# arm_v4.net
KiCad netlist of a schematic drawn in Altium Designer
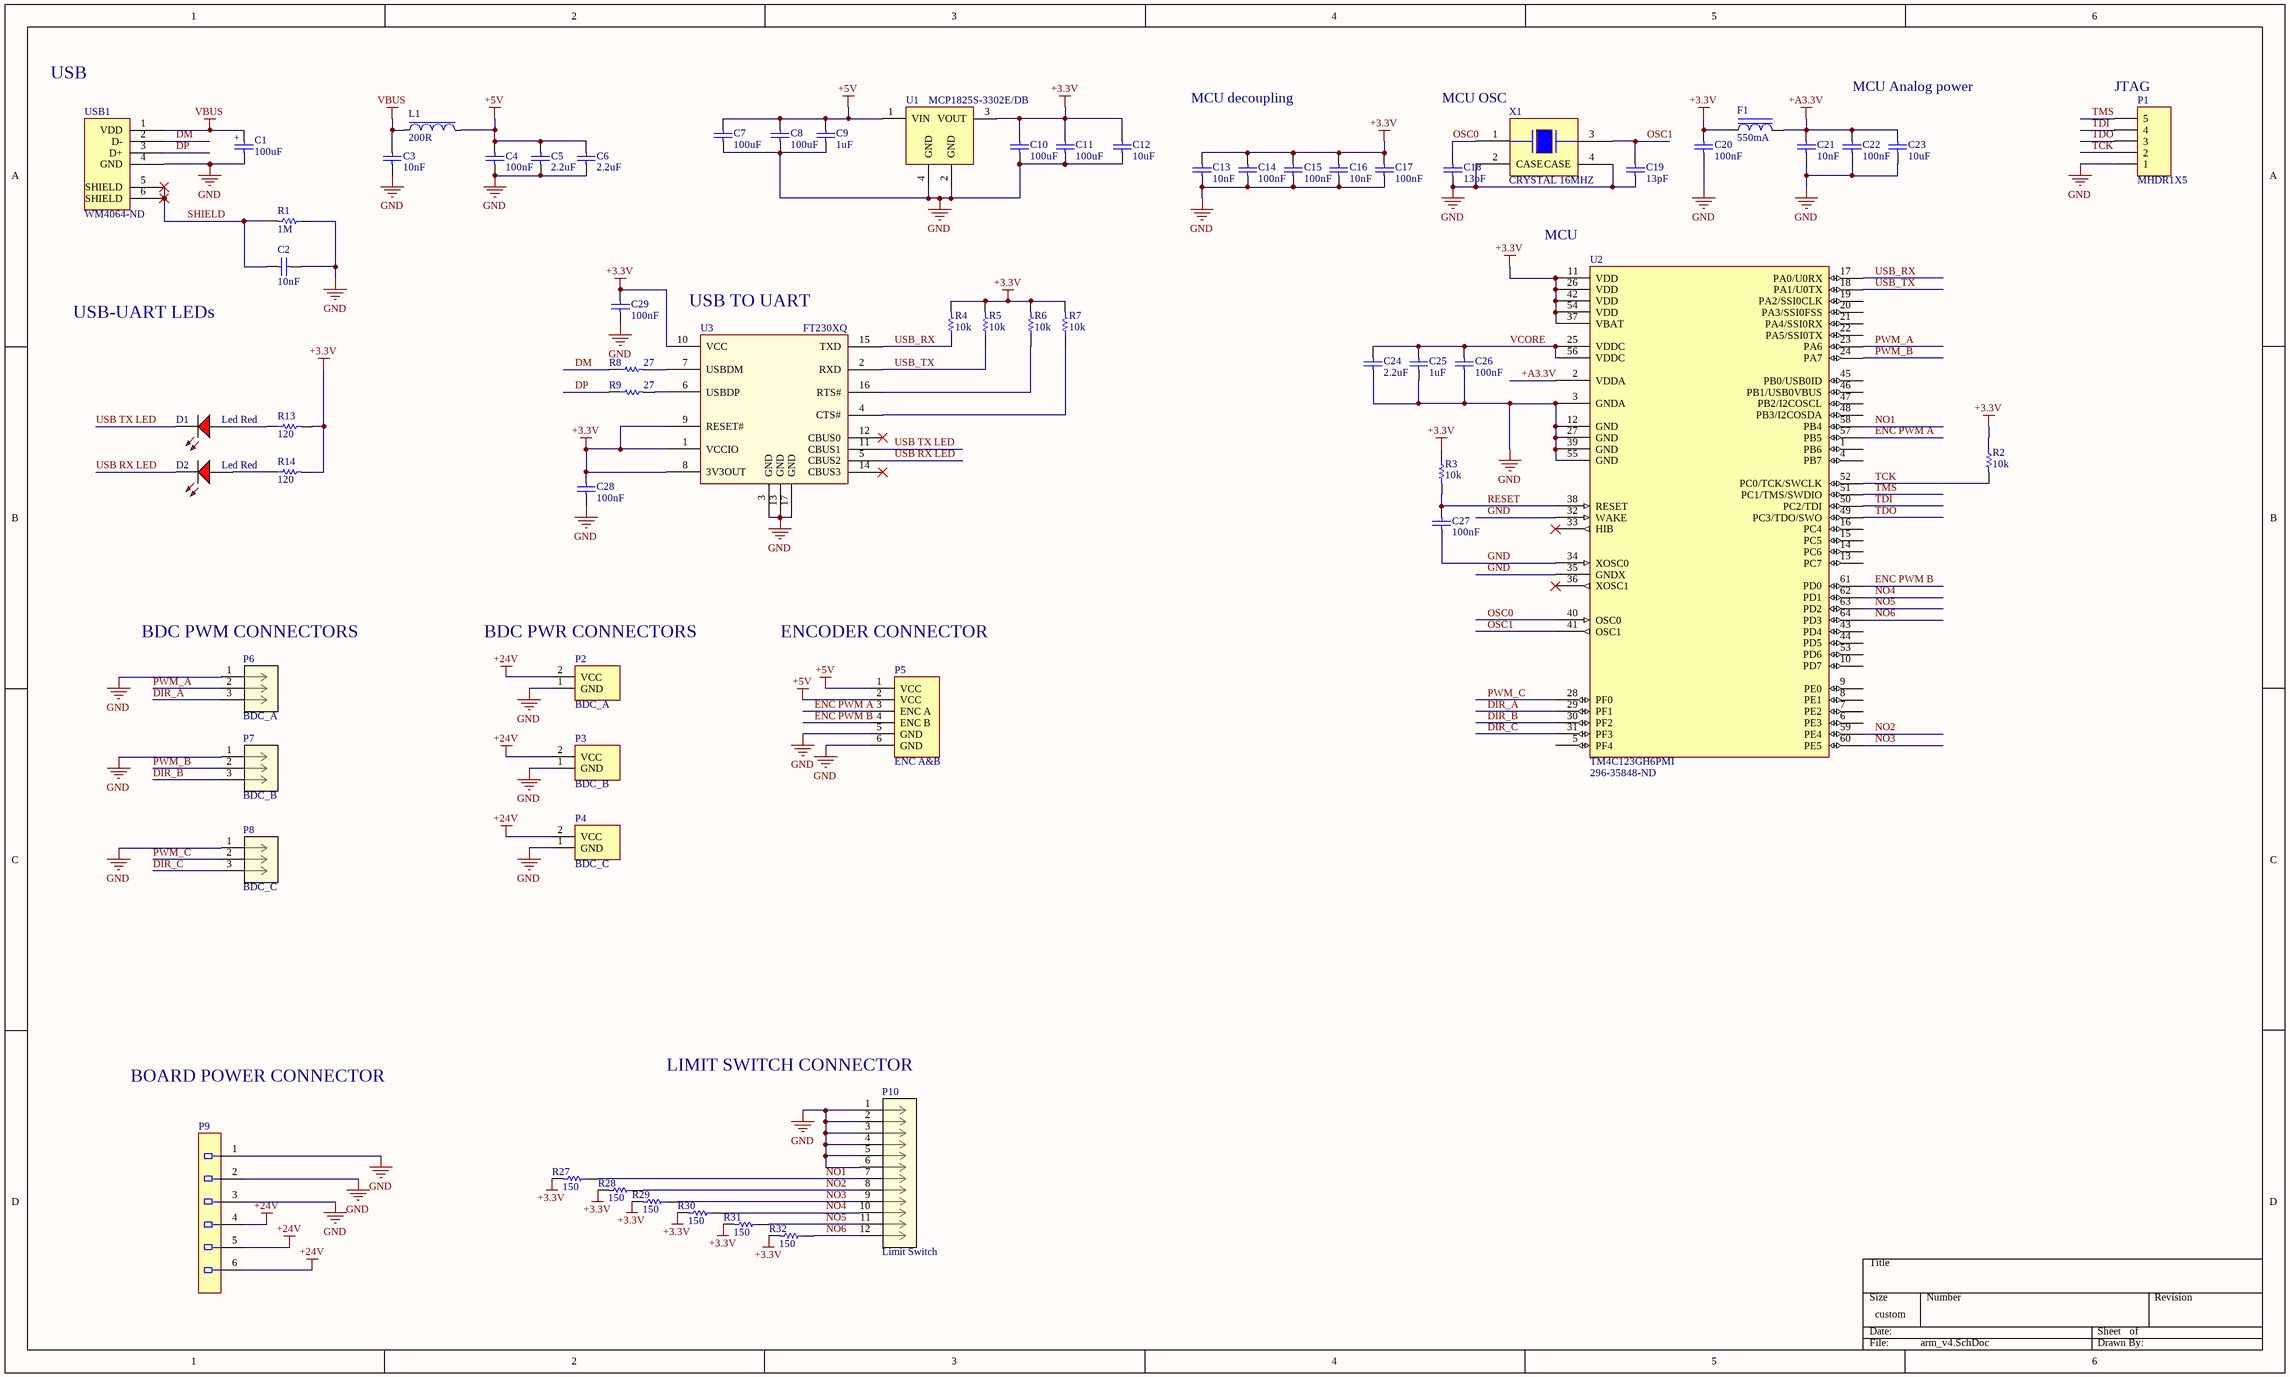
[diagram p0: arm_v4.SchDoc]

(export (version "E")
  (design (tool "Eeschema 10.0.6"))
  (components
    (comp (ref "C1")
      (value "100uF")
      (footprint "CapAlu6.3mmx12.5mm")
      (description "Capacitor 35v 100uF 6.3mm")
      (fields
        (field (name "MANUFACTURER") "Nichicon")
        (field (name "MANUFACTURER PART NUMBER") "UHV1V101MED")
      )
      (libsource (lib "Capacitors") (part "100uF_35v_6.3x12.5"))
    )
    (comp (ref "C2")
      (value "10nF")
      (footprint "CAP_1206")
      (description "CAP CER 10000PF 500V X7R 1206")
      (fields
        (field (name "MANUFACTURER") "Samsung Electro-Mechanics America, Inc")
        (field (name "MANUFACTURER PART NUMBER") "CL31B103KGFNNNE")
      )
      (libsource (lib "Capacitors") (part "10nF_500V_1206"))
    )
    (comp (ref "C3")
      (value "10nF")
      (footprint "CAP_0402_M")
      (description "CAP CER 10000PF 50V 10% X7R 0402")
      (fields
        (field (name "MANUFACTURER") "Kemet")
        (field (name "MANUFACTURER PART NUMBER") "C0402C103K5RACTU")
      )
      (libsource (lib "Capacitors") (part "10nF_50V_0402"))
    )
    (comp (ref "C4")
      (value "100nF")
      (footprint "CAP_0402_M")
      (description "CAP CER 100NF 50V 20% X5R 0402")
      (fields
        (field (name "MANUFACTURER") "TDK Corporation")
        (field (name "MANUFACTURER PART NUMBER") "C1005X5R1H104M050BB")
      )
      (libsource (lib "Capacitors") (part "100nF_50V_0402"))
    )
    (comp (ref "C5")
      (value "2.2uF")
      (footprint "CAP_0402_M")
      (description "CAP CER 2.2UF 10V 20% X5R 0402")
      (fields
        (field (name "MANUFACTURER") "Taiyo Yuden")
        (field (name "MANUFACTURER PART NUMBER") "LMK105BJ225MV-F")
      )
      (libsource (lib "Capacitors") (part "2.2uF_10V_0402"))
    )
    (comp (ref "C6")
      (value "2.2uF")
      (footprint "CAP_0402_M")
      (description "CAP CER 2.2UF 10V 20% X5R 0402")
      (fields
        (field (name "MANUFACTURER") "Taiyo Yuden")
        (field (name "MANUFACTURER PART NUMBER") "LMK105BJ225MV-F")
      )
      (libsource (lib "Capacitors") (part "2.2uF_10V_0402"))
    )
    (comp (ref "C7")
      (value "100uF")
      (footprint "CAP_1206")
      (description "CAP CER 100UF 6.3V X5R 1206")
      (fields
        (field (name "MANUFACTURER") "Murata Electronics North America")
        (field (name "MANUFACTURER PART NUMBER") "GRM31CR60J107ME39L")
      )
      (libsource (lib "Capacitors") (part "100uF_6.3v_1206_X5R"))
    )
    (comp (ref "C8")
      (value "100uF")
      (footprint "CAP_1206")
      (description "CAP CER 100UF 6.3V X5R 1206")
      (fields
        (field (name "MANUFACTURER") "Murata Electronics North America")
        (field (name "MANUFACTURER PART NUMBER") "GRM31CR60J107ME39L")
      )
      (libsource (lib "Capacitors") (part "100uF_6.3v_1206_X5R"))
    )
    (comp (ref "C9")
      (value "1uF")
      (footprint "CAP_0402_M")
      (description "CAP CER 1UF 25V 10% X5R 0402")
      (fields
        (field (name "MANUFACTURER") "TDK Corporation")
        (field (name "MANUFACTURER PART NUMBER") "C1005X5R1E105K050BC")
      )
      (libsource (lib "Capacitors") (part "1uF_25V_0402"))
    )
    (comp (ref "C10")
      (value "100uF")
      (footprint "CAP_1206")
      (description "CAP CER 100UF 6.3V X5R 1206")
      (fields
        (field (name "MANUFACTURER") "Murata Electronics North America")
        (field (name "MANUFACTURER PART NUMBER") "GRM31CR60J107ME39L")
      )
      (libsource (lib "Capacitors") (part "100uF_6.3v_1206_X5R"))
    )
    (comp (ref "C11")
      (value "100uF")
      (footprint "CAP_1206")
      (description "CAP CER 100UF 6.3V X5R 1206")
      (fields
        (field (name "MANUFACTURER") "Murata Electronics North America")
        (field (name "MANUFACTURER PART NUMBER") "GRM31CR60J107ME39L")
      )
      (libsource (lib "Capacitors") (part "100uF_6.3v_1206_X5R"))
    )
    (comp (ref "C12")
      (value "10uF")
      (footprint "CAP_0603")
      (description "CAP CER 10UF 10V 20% X5R 0603")
      (fields
        (field (name "MANUFACTURER") "Taiyo Yuden")
        (field (name "MANUFACTURER PART NUMBER") "LMK107BBJ106MAHT")
      )
      (libsource (lib "Capacitors") (part "10uF_10V_0603"))
    )
    (comp (ref "C13")
      (value "10nF")
      (footprint "CAP_0402_M")
      (description "CAP CER 10000PF 50V 10% X7R 0402")
      (fields
        (field (name "MANUFACTURER") "Kemet")
        (field (name "MANUFACTURER PART NUMBER") "C0402C103K5RACTU")
      )
      (libsource (lib "Capacitors") (part "10nF_50V_0402"))
    )
    (comp (ref "C14")
      (value "100nF")
      (footprint "CAP_0402_M")
      (description "CAP CER 100NF 50V 20% X5R 0402")
      (fields
        (field (name "MANUFACTURER") "TDK Corporation")
        (field (name "MANUFACTURER PART NUMBER") "C1005X5R1H104M050BB")
      )
      (libsource (lib "Capacitors") (part "100nF_50V_0402"))
    )
    (comp (ref "C15")
      (value "100nF")
      (footprint "CAP_0402_M")
      (description "CAP CER 100NF 50V 20% X5R 0402")
      (fields
        (field (name "MANUFACTURER") "TDK Corporation")
        (field (name "MANUFACTURER PART NUMBER") "C1005X5R1H104M050BB")
      )
      (libsource (lib "Capacitors") (part "100nF_50V_0402"))
    )
    (comp (ref "C16")
      (value "10nF")
      (footprint "CAP_0402_M")
      (description "CAP CER 10000PF 50V 10% X7R 0402")
      (fields
        (field (name "MANUFACTURER") "Kemet")
        (field (name "MANUFACTURER PART NUMBER") "C0402C103K5RACTU")
      )
      (libsource (lib "Capacitors") (part "10nF_50V_0402"))
    )
    (comp (ref "C17")
      (value "100nF")
      (footprint "CAP_0402_M")
      (description "CAP CER 100NF 50V 20% X5R 0402")
      (fields
        (field (name "MANUFACTURER") "TDK Corporation")
        (field (name "MANUFACTURER PART NUMBER") "C1005X5R1H104M050BB")
      )
      (libsource (lib "Capacitors") (part "100nF_50V_0402"))
    )
    (comp (ref "C18")
      (value "13pF")
      (footprint "CAP_0402_M")
      (description "CAP CER 13PF 50V 5% NP0 0402")
      (fields
        (field (name "MANUFACTURER") "Samsung Electro-Mechanics America, Inc")
        (field (name "MANUFACTURER PART NUMBER") "CL05C130JB5NNNC")
      )
      (libsource (lib "Capacitors") (part "13pF_50V_0402"))
    )
    (comp (ref "C19")
      (value "13pF")
      (footprint "CAP_0402_M")
      (description "CAP CER 13PF 50V 5% NP0 0402")
      (fields
        (field (name "MANUFACTURER") "Samsung Electro-Mechanics America, Inc")
        (field (name "MANUFACTURER PART NUMBER") "CL05C130JB5NNNC")
      )
      (libsource (lib "Capacitors") (part "13pF_50V_0402"))
    )
    (comp (ref "C20")
      (value "100nF")
      (footprint "CAP_0402_M")
      (description "CAP CER 100NF 50V 20% X5R 0402")
      (fields
        (field (name "MANUFACTURER") "TDK Corporation")
        (field (name "MANUFACTURER PART NUMBER") "C1005X5R1H104M050BB")
      )
      (libsource (lib "Capacitors") (part "100nF_50V_0402"))
    )
    (comp (ref "C21")
      (value "10nF")
      (footprint "CAP_0402_M")
      (description "CAP CER 10000PF 50V 10% X7R 0402")
      (fields
        (field (name "MANUFACTURER") "Kemet")
        (field (name "MANUFACTURER PART NUMBER") "C0402C103K5RACTU")
      )
      (libsource (lib "Capacitors") (part "10nF_50V_0402"))
    )
    (comp (ref "C22")
      (value "100nF")
      (footprint "CAP_0402_M")
      (description "CAP CER 100NF 50V 20% X5R 0402")
      (fields
        (field (name "MANUFACTURER") "TDK Corporation")
        (field (name "MANUFACTURER PART NUMBER") "C1005X5R1H104M050BB")
      )
      (libsource (lib "Capacitors") (part "100nF_50V_0402"))
    )
    (comp (ref "C23")
      (value "10uF")
      (footprint "CAP_0603")
      (description "CAP CER 10UF 10V 20% X5R 0603")
      (fields
        (field (name "MANUFACTURER") "Taiyo Yuden")
        (field (name "MANUFACTURER PART NUMBER") "LMK107BBJ106MAHT")
      )
      (libsource (lib "Capacitors") (part "10uF_10V_0603"))
    )
    (comp (ref "C24")
      (value "2.2uF")
      (footprint "CAP_0603")
      (description "CAP CER 2.2UF 35V 10% X5R 0603")
      (fields
        (field (name "MANUFACTURER") "Murata Electronics North America")
        (field (name "MANUFACTURER PART NUMBER") "GRM188R6YA225KA12D")
      )
      (libsource (lib "Capacitors") (part "2.2uF_35V_0603"))
    )
    (comp (ref "C25")
      (value "1uF")
      (footprint "CAP_0402_M")
      (description "CAP CER 1UF 25V 10% X5R 0402")
      (fields
        (field (name "MANUFACTURER") "TDK Corporation")
        (field (name "MANUFACTURER PART NUMBER") "C1005X5R1E105K050BC")
      )
      (libsource (lib "Capacitors") (part "1uF_25V_0402"))
    )
    (comp (ref "C26")
      (value "100nF")
      (footprint "CAP_0402_M")
      (description "CAP CER 100NF 50V 20% X5R 0402")
      (fields
        (field (name "MANUFACTURER") "TDK Corporation")
        (field (name "MANUFACTURER PART NUMBER") "C1005X5R1H104M050BB")
      )
      (libsource (lib "Capacitors") (part "100nF_50V_0402"))
    )
    (comp (ref "C27")
      (value "100nF")
      (footprint "CAP_0402_M")
      (description "CAP CER 100NF 50V 20% X5R 0402")
      (fields
        (field (name "MANUFACTURER") "TDK Corporation")
        (field (name "MANUFACTURER PART NUMBER") "C1005X5R1H104M050BB")
      )
      (libsource (lib "Capacitors") (part "100nF_50V_0402"))
    )
    (comp (ref "C28")
      (value "100nF")
      (footprint "CAP_0402_M")
      (description "CAP CER 100NF 50V 20% X5R 0402")
      (fields
        (field (name "MANUFACTURER") "TDK Corporation")
        (field (name "MANUFACTURER PART NUMBER") "C1005X5R1H104M050BB")
      )
      (libsource (lib "Capacitors") (part "100nF_50V_0402"))
    )
    (comp (ref "C29")
      (value "100nF")
      (footprint "CAP_0402_M")
      (description "CAP CER 100NF 50V 20% X5R 0402")
      (fields
        (field (name "MANUFACTURER") "TDK Corporation")
        (field (name "MANUFACTURER PART NUMBER") "C1005X5R1H104M050BB")
      )
      (libsource (lib "Capacitors") (part "100nF_50V_0402"))
    )
    (comp (ref "D1")
      (value "Led Red")
      (footprint "TOPLED 0805")
      (description "LED TOPLED 630NM SUP RED CLR SMD")
      (fields
        (field (name "MANUFACTURER") "OSRAM Opto Semiconductors Inc")
        (field (name "MANUFACTURER PART NUMBER") "LS M67K-H2L1-1-Z")
      )
      (libsource (lib "Diodes") (part "TOPLED 0803"))
    )
    (comp (ref "D2")
      (value "Led Red")
      (footprint "TOPLED 0805")
      (description "LED TOPLED 630NM SUP RED CLR SMD")
      (fields
        (field (name "MANUFACTURER") "OSRAM Opto Semiconductors Inc")
        (field (name "MANUFACTURER PART NUMBER") "LS M67K-H2L1-1-Z")
      )
      (libsource (lib "Diodes") (part "TOPLED 0803"))
    )
    (comp (ref "F1")
      (value "550mA")
      (footprint "RES_0402_M")
      (description "FERRITE CHIP 40 OHM 550MA 0402")
      (fields
        (field (name "MANUFACTURER") "TDK Corporation")
        (field (name "MANUFACTURER PART NUMBER") "MMZ1005Y400CT000")
      )
      (libsource (lib "Resistors") (part "40O_550mA_0402"))
    )
    (comp (ref "L1")
      (value "200R")
      (footprint "IND_0603")
      (description "FILTER CHIP 220 OHM 2A 0603")
      (fields
        (field (name "MANUFACTURER") "Murata Electronics North America")
        (field (name "MANUFACTURER PART NUMBER") "BLM18EG221SN1D")
      )
      (libsource (lib "Inductors") (part "Ferrite_200 ohms_2A"))
    )
    (comp (ref "P1")
      (value "MHDR1X5")
      (footprint "MHDR1X5")
      (description "Header, 5-Pin")
      (fields (field (name "PUBLISHER") "Altium Limited"))
      (libsource (lib "Miscellaneous Connectors") (part "MHDR1X5"))
    )
    (comp (ref "P2")
      (value "BDC_A")
      (footprint "SamacSys:436500227")
      (description "Connector")
      (fields (field (name "MANUFACTURER_PART_NUMBER") "43650-0227"))
      (libsource (lib "*") (part "43650-0227"))
    )
    (comp (ref "P3")
      (value "BDC_B")
      (footprint "SamacSys:436500227")
      (description "Connector")
      (fields (field (name "MANUFACTURER_PART_NUMBER") "43650-0227"))
      (libsource (lib "*") (part "43650-0227"))
    )
    (comp (ref "P4")
      (value "BDC_C")
      (footprint "SamacSys:436500227")
      (description "Connector")
      (fields (field (name "MANUFACTURER_PART_NUMBER") "43650-0227"))
      (libsource (lib "*") (part "43650-0227"))
    )
    (comp (ref "P5")
      (value "ENC A&B")
      (footprint "SamacSys:1053091106")
      (description "Connector")
      (fields (field (name "MANUFACTURER_PART_NUMBER") "105309-1106"))
      (libsource (lib "*") (part "105309-1106"))
    )
    (comp (ref "P6")
      (value "BDC_A")
      (footprint "CON_1053091203")
      (description "No Description Available")
      (fields
        (field (name "MANUFACTURER_PART_NUMBER") "1053091203")
        (field (name "COPYRIGHT") "Copyright (C) 2021 Accelerated Designs. All rights reserved")
      )
      (libsource (lib "Molex 1053091203") (part "1053091203"))
    )
    (comp (ref "P7")
      (value "BDC_B")
      (footprint "CON_1053091203")
      (description "No Description Available")
      (fields
        (field (name "MANUFACTURER_PART_NUMBER") "1053091203")
        (field (name "COPYRIGHT") "Copyright (C) 2021 Accelerated Designs. All rights reserved")
      )
      (libsource (lib "Molex 1053091203") (part "1053091203"))
    )
    (comp (ref "P8")
      (value "BDC_C")
      (footprint "CON_1053091203")
      (description "No Description Available")
      (fields
        (field (name "MANUFACTURER_PART_NUMBER") "1053091203")
        (field (name "COPYRIGHT") "Copyright (C) 2021 Accelerated Designs. All rights reserved")
      )
      (libsource (lib "Molex 1053091203") (part "1053091203"))
    )
    (comp (ref "P9") (value "76825-0006") (libsource (lib "Molex 76825-0006") (part "76825-0006")))
    (comp (ref "P10")
      (value "Limit Switch")
      (footprint "CON_1053141112")
      (description "No Description Available")
      (fields
        (field (name "MANUFACTURER_PART_NUMBER") "1053141112")
        (field (name "COPYRIGHT") "Copyright (C) 2018 Accelerated Designs. All rights reserved")
      )
      (libsource (lib "Molex 1053141112") (part "1053141112"))
    )
    (comp (ref "R1")
      (value "1M")
      (footprint "RES_1206")
      (description "RES SMD 1M OHM 5% 1/4W 1206")
      (fields
        (field (name "MANUFACTURER") "Panasonic Electronic Components")
        (field (name "MANUFACTURER PART NUMBER") "ERJ-8GEYJ105V")
      )
      (libsource (lib "Resistors") (part "1M_5%_1206"))
    )
    (comp (ref "R2")
      (value "10k")
      (footprint "RES_0402_M")
      (description "RES SMD 10K OHM 1% 1/10W 0402")
      (fields
        (field (name "MANUFACTURER") "Panasonic Electronic Components")
        (field (name "MANUFACTURER PART NUMBER") "ERJ-2RKF1002X")
      )
      (libsource (lib "Resistors") (part "10k_1%_0402"))
    )
    (comp (ref "R3")
      (value "10k")
      (footprint "RES_0402_M")
      (description "RES SMD 10K OHM 1% 1/10W 0402")
      (fields
        (field (name "MANUFACTURER") "Panasonic Electronic Components")
        (field (name "MANUFACTURER PART NUMBER") "ERJ-2RKF1002X")
      )
      (libsource (lib "Resistors") (part "10k_1%_0402"))
    )
    (comp (ref "R4")
      (value "10k")
      (footprint "RES_0402_M")
      (description "RES SMD 10K OHM 1% 1/10W 0402")
      (fields
        (field (name "MANUFACTURER") "Panasonic Electronic Components")
        (field (name "MANUFACTURER PART NUMBER") "ERJ-2RKF1002X")
      )
      (libsource (lib "Resistors") (part "10k_1%_0402"))
    )
    (comp (ref "R5")
      (value "10k")
      (footprint "RES_0402_M")
      (description "RES SMD 10K OHM 1% 1/10W 0402")
      (fields
        (field (name "MANUFACTURER") "Panasonic Electronic Components")
        (field (name "MANUFACTURER PART NUMBER") "ERJ-2RKF1002X")
      )
      (libsource (lib "Resistors") (part "10k_1%_0402"))
    )
    (comp (ref "R6")
      (value "10k")
      (footprint "RES_0402_M")
      (description "RES SMD 10K OHM 1% 1/10W 0402")
      (fields
        (field (name "MANUFACTURER") "Panasonic Electronic Components")
        (field (name "MANUFACTURER PART NUMBER") "ERJ-2RKF1002X")
      )
      (libsource (lib "Resistors") (part "10k_1%_0402"))
    )
    (comp (ref "R7")
      (value "10k")
      (footprint "RES_0402_M")
      (description "RES SMD 10K OHM 1% 1/10W 0402")
      (fields
        (field (name "MANUFACTURER") "Panasonic Electronic Components")
        (field (name "MANUFACTURER PART NUMBER") "ERJ-2RKF1002X")
      )
      (libsource (lib "Resistors") (part "10k_1%_0402"))
    )
    (comp (ref "R8")
      (value "27")
      (footprint "RES_0402_M")
      (description "RES SMD 27 OHM 1% 1/10W 0402")
      (fields
        (field (name "MANUFACTURER") "Panasonic Electronic Components")
        (field (name "MANUFACTURER PART NUMBER") "ERJ-2RKF27R0X")
      )
      (libsource (lib "Resistors") (part "27_1%_0402"))
    )
    (comp (ref "R9")
      (value "27")
      (footprint "RES_0402_M")
      (description "RES SMD 27 OHM 1% 1/10W 0402")
      (fields
        (field (name "MANUFACTURER") "Panasonic Electronic Components")
        (field (name "MANUFACTURER PART NUMBER") "ERJ-2RKF27R0X")
      )
      (libsource (lib "Resistors") (part "27_1%_0402"))
    )
    (comp (ref "R13")
      (value "120")
      (footprint "RES_0402_M")
      (description "RES SMD 120 OHM 1% 1/10W 0402")
      (fields
        (field (name "MANUFACTURER") "Panasonic Electronic Components")
        (field (name "MANUFACTURER PART NUMBER") "ERJ-2RKF1200X")
      )
      (libsource (lib "Resistors") (part "120_1%_0402"))
    )
    (comp (ref "R14")
      (value "120")
      (footprint "RES_0402_M")
      (description "RES SMD 120 OHM 1% 1/10W 0402")
      (fields
        (field (name "MANUFACTURER") "Panasonic Electronic Components")
        (field (name "MANUFACTURER PART NUMBER") "ERJ-2RKF1200X")
      )
      (libsource (lib "Resistors") (part "120_1%_0402"))
    )
    (comp (ref "R27")
      (value "150")
      (footprint "RES_0402_M")
      (description "RES SMD 10K OHM 1% 1/10W 0402")
      (fields
        (field (name "MANUFACTURER") "Panasonic Electronic Components")
        (field (name "MANUFACTURER PART NUMBER") "ERJ-2RKF1002X")
      )
      (libsource (lib "Resistors") (part "10k_1%_0402"))
    )
    (comp (ref "R28")
      (value "150")
      (footprint "RES_0402_M")
      (description "RES SMD 10K OHM 1% 1/10W 0402")
      (fields
        (field (name "MANUFACTURER") "Panasonic Electronic Components")
        (field (name "MANUFACTURER PART NUMBER") "ERJ-2RKF1002X")
      )
      (libsource (lib "Resistors") (part "10k_1%_0402"))
    )
    (comp (ref "R29")
      (value "150")
      (footprint "RES_0402_M")
      (description "RES SMD 10K OHM 1% 1/10W 0402")
      (fields
        (field (name "MANUFACTURER") "Panasonic Electronic Components")
        (field (name "MANUFACTURER PART NUMBER") "ERJ-2RKF1002X")
      )
      (libsource (lib "Resistors") (part "10k_1%_0402"))
    )
    (comp (ref "R30")
      (value "150")
      (footprint "RES_0402_M")
      (description "RES SMD 10K OHM 1% 1/10W 0402")
      (fields
        (field (name "MANUFACTURER") "Panasonic Electronic Components")
        (field (name "MANUFACTURER PART NUMBER") "ERJ-2RKF1002X")
      )
      (libsource (lib "Resistors") (part "10k_1%_0402"))
    )
    (comp (ref "R31")
      (value "150")
      (footprint "RES_0402_M")
      (description "RES SMD 10K OHM 1% 1/10W 0402")
      (fields
        (field (name "MANUFACTURER") "Panasonic Electronic Components")
        (field (name "MANUFACTURER PART NUMBER") "ERJ-2RKF1002X")
      )
      (libsource (lib "Resistors") (part "10k_1%_0402"))
    )
    (comp (ref "R32")
      (value "150")
      (footprint "RES_0402_M")
      (description "RES SMD 10K OHM 1% 1/10W 0402")
      (fields
        (field (name "MANUFACTURER") "Panasonic Electronic Components")
        (field (name "MANUFACTURER PART NUMBER") "ERJ-2RKF1002X")
      )
      (libsource (lib "Resistors") (part "10k_1%_0402"))
    )
    (comp (ref "U1")
      (value "MCP1825S-3302E/DB")
      (footprint "SOT230P700X180-4N")
      (description "500 mA, Low Voltage, Low Quiescent Current LDO Regulator")
      (fields (field (name "MANUFACTURER") "Microchip Technology"))
      (libsource (lib "ICs") (part "MCP1825S-3302E/DB"))
    )
    (comp (ref "U2")
      (value "TM4C123GH6PMI")
      (footprint "TSQFP50P1200X1200X120-64N")
      (description "Tiva TM4C123GH6PM Microcontroller ARM Cortex 80 MHz FPU")
      (fields (field (name "SUPPLIER PART NUMBER 1") "296-35848-ND"))
      (libsource (lib "ICs") (part "TM4C123GH6PMI"))
    )
    (comp (ref "U3")
      (value "FT230XQ")
      (footprint "QFN65P400X400X80_HS-17N")
      (description "IC USB SERIAL BASIC UART 16QFN")
      (fields
        (field (name "MANUFACTURER") "FTDI, Future Technology Devices International Ltd")
        (field (name "MANUFACTURER PART NUMBER") "FT230XQ-R")
      )
      (libsource (lib "ICs") (part "FT230XQ-R"))
    )
    (comp (ref "USB1")
      (value "USB type-B jack")
      (footprint "USB2.5-2H4E")
      (fields (field (name "SUPPLIER PART NUMBER 1") "WM4064-ND"))
      (libsource (lib "Connectors") (part "MOLEX 0670688010"))
    )
    (comp (ref "X1")
      (value "CRYSTAL 16MHZ")
      (footprint "CRYSTAL_3.2x2.5")
      (description "CRYSTAL 16MHZ 20PF SMD")
      (fields
        (field (name "MANUFACTURER") "CTS-Frequency Controls")
        (field (name "MANUFACTURER PART NUMBER") "403C35E16M00000")
      )
      (libsource (lib "ICs") (part "403C35E16M00000"))
    )
  )
  (nets
    (net (code "1") (name "+3.3V") (class "Default")
      (node (ref "C10") (pin "1") (pinfunction "1_1") (pintype "passive"))
      (node (ref "C11") (pin "1") (pinfunction "1_1") (pintype "passive"))
      (node (ref "C12") (pin "1") (pinfunction "1_1") (pintype "passive"))
      (node (ref "C13") (pin "2") (pinfunction "2_2") (pintype "passive"))
      (node (ref "C14") (pin "2") (pinfunction "2_2") (pintype "passive"))
      (node (ref "C15") (pin "2") (pinfunction "2_2") (pintype "passive"))
      (node (ref "C16") (pin "2") (pinfunction "2_2") (pintype "passive"))
      (node (ref "C17") (pin "2") (pinfunction "2_2") (pintype "passive"))
      (node (ref "C20") (pin "2") (pinfunction "2_2") (pintype "passive"))
      (node (ref "C28") (pin "2") (pinfunction "2_2") (pintype "passive"))
      (node (ref "C29") (pin "2") (pinfunction "2_2") (pintype "passive"))
      (node (ref "F1") (pin "1") (pinfunction "1_1") (pintype "passive"))
      (node (ref "R13") (pin "2") (pinfunction "2_2") (pintype "passive"))
      (node (ref "R14") (pin "2") (pinfunction "2_2") (pintype "passive"))
      (node (ref "R2") (pin "1") (pinfunction "1_1") (pintype "passive"))
      (node (ref "R27") (pin "2") (pinfunction "2_2") (pintype "passive"))
      (node (ref "R28") (pin "2") (pinfunction "2_2") (pintype "passive"))
      (node (ref "R29") (pin "2") (pinfunction "2_2") (pintype "passive"))
      (node (ref "R3") (pin "1") (pinfunction "1_1") (pintype "passive"))
      (node (ref "R30") (pin "2") (pinfunction "2_2") (pintype "passive"))
      (node (ref "R31") (pin "2") (pinfunction "2_2") (pintype "passive"))
      (node (ref "R32") (pin "2") (pinfunction "2_2") (pintype "passive"))
      (node (ref "R4") (pin "2") (pinfunction "2_2") (pintype "passive"))
      (node (ref "R5") (pin "2") (pinfunction "2_2") (pintype "passive"))
      (node (ref "R6") (pin "2") (pinfunction "2_2") (pintype "passive"))
      (node (ref "R7") (pin "2") (pinfunction "2_2") (pintype "passive"))
      (node (ref "U1") (pin "3") (pinfunction "VOUT_3") (pintype "power_in"))
      (node (ref "U2") (pin "11") (pinfunction "VDD_11") (pintype "power_in"))
      (node (ref "U2") (pin "26") (pinfunction "VDD_26") (pintype "power_in"))
      (node (ref "U2") (pin "37") (pinfunction "VBAT_37") (pintype "power_in"))
      (node (ref "U2") (pin "42") (pinfunction "VDD_42") (pintype "power_in"))
      (node (ref "U2") (pin "54") (pinfunction "VDD_54") (pintype "power_in"))
      (node (ref "U3") (pin "1") (pinfunction "VCCIO_1") (pintype "passive"))
      (node (ref "U3") (pin "10") (pinfunction "VCC_10") (pintype "passive"))
      (node (ref "U3") (pin "8") (pinfunction "3V3OUT_8") (pintype "passive"))
      (node (ref "U3") (pin "9") (pinfunction "RESET#_9") (pintype "passive"))
    )
    (net (code "2") (name "+5V") (class "Default")
      (node (ref "C4") (pin "2") (pinfunction "2_2") (pintype "passive"))
      (node (ref "C5") (pin "2") (pinfunction "2_2") (pintype "passive"))
      (node (ref "C6") (pin "2") (pinfunction "2_2") (pintype "passive"))
      (node (ref "C7") (pin "1") (pinfunction "1_1") (pintype "passive"))
      (node (ref "C8") (pin "1") (pinfunction "1_1") (pintype "passive"))
      (node (ref "C9") (pin "2") (pinfunction "2_2") (pintype "passive"))
      (node (ref "L1") (pin "2") (pinfunction "2_2") (pintype "passive"))
      (node (ref "P5") (pin "1") (pinfunction "VCC_1") (pintype "passive"))
      (node (ref "P5") (pin "2") (pinfunction "VCC_2") (pintype "passive"))
      (node (ref "U1") (pin "1") (pinfunction "VIN_1") (pintype "power_in"))
    )
    (net (code "3") (name "+24V") (class "Default")
      (node (ref "P2") (pin "2") (pinfunction "VCC_2") (pintype "passive"))
      (node (ref "P3") (pin "2") (pinfunction "VCC_2") (pintype "passive"))
      (node (ref "P4") (pin "2") (pinfunction "VCC_2") (pintype "passive"))
      (node (ref "P9") (pin "4") (pinfunction "4_4") (pintype "passive"))
      (node (ref "P9") (pin "5") (pinfunction "5_5") (pintype "passive"))
      (node (ref "P9") (pin "6") (pinfunction "6_6") (pintype "passive"))
    )
    (net (code "4") (name "+A3.3V") (class "Default")
      (node (ref "C21") (pin "2") (pinfunction "2_2") (pintype "passive"))
      (node (ref "C22") (pin "2") (pinfunction "2_2") (pintype "passive"))
      (node (ref "C23") (pin "2") (pinfunction "2_2") (pintype "passive"))
      (node (ref "F1") (pin "2") (pinfunction "2_2") (pintype "passive"))
      (node (ref "U2") (pin "2") (pinfunction "VDDA_2") (pintype "power_in"))
    )
    (net (code "5") (name "/DIR_A") (class "Default")
      (node (ref "P6") (pin "3") (pinfunction "DIR_3") (pintype "passive"))
      (node (ref "U2") (pin "29") (pinfunction "PF1_29") (pintype "bidirectional"))
    )
    (net (code "6") (name "/DIR_B") (class "Default")
      (node (ref "P7") (pin "3") (pinfunction "DIR_3") (pintype "passive"))
      (node (ref "U2") (pin "30") (pinfunction "PF2_30") (pintype "bidirectional"))
    )
    (net (code "7") (name "/DIR_C") (class "Default")
      (node (ref "P8") (pin "3") (pinfunction "DIR_3") (pintype "passive"))
      (node (ref "U2") (pin "31") (pinfunction "PF3_31") (pintype "bidirectional"))
    )
    (net (code "8") (name "/DM") (class "Default")
      (node (ref "R8") (pin "1") (pinfunction "1_1") (pintype "passive"))
      (node (ref "USB1") (pin "2") (pinfunction "D-_2") (pintype "passive"))
    )
    (net (code "9") (name "/DP") (class "Default")
      (node (ref "R9") (pin "1") (pinfunction "1_1") (pintype "passive"))
      (node (ref "USB1") (pin "3") (pinfunction "D+_3") (pintype "passive"))
    )
    (net (code "10") (name "/ENC PWM A") (class "Default")
      (node (ref "P5") (pin "3") (pinfunction "ENC_A_3") (pintype "passive"))
      (node (ref "U2") (pin "57") (pinfunction "PB5_57") (pintype "bidirectional"))
    )
    (net (code "11") (name "/ENC PWM B") (class "Default")
      (node (ref "P5") (pin "4") (pinfunction "ENC_B_4") (pintype "passive"))
      (node (ref "U2") (pin "61") (pinfunction "PD0_61") (pintype "bidirectional"))
    )
    (net (code "12") (name "/NO1") (class "Default")
      (node (ref "P10") (pin "7") (pinfunction "7_7") (pintype "passive"))
      (node (ref "R27") (pin "1") (pinfunction "1_1") (pintype "passive"))
      (node (ref "U2") (pin "58") (pinfunction "PB4_58") (pintype "bidirectional"))
    )
    (net (code "13") (name "/NO2") (class "Default")
      (node (ref "P10") (pin "8") (pinfunction "8_8") (pintype "passive"))
      (node (ref "R28") (pin "1") (pinfunction "1_1") (pintype "passive"))
      (node (ref "U2") (pin "59") (pinfunction "PE4_59") (pintype "bidirectional"))
    )
    (net (code "14") (name "/NO3") (class "Default")
      (node (ref "P10") (pin "9") (pinfunction "9_9") (pintype "passive"))
      (node (ref "R29") (pin "1") (pinfunction "1_1") (pintype "passive"))
      (node (ref "U2") (pin "60") (pinfunction "PE5_60") (pintype "bidirectional"))
    )
    (net (code "15") (name "/NO4") (class "Default")
      (node (ref "P10") (pin "10") (pinfunction "10_10") (pintype "passive"))
      (node (ref "R30") (pin "1") (pinfunction "1_1") (pintype "passive"))
      (node (ref "U2") (pin "62") (pinfunction "PD1_62") (pintype "bidirectional"))
    )
    (net (code "16") (name "/NO5") (class "Default")
      (node (ref "P10") (pin "11") (pinfunction "11_11") (pintype "passive"))
      (node (ref "R31") (pin "1") (pinfunction "1_1") (pintype "passive"))
      (node (ref "U2") (pin "63") (pinfunction "PD2_63") (pintype "bidirectional"))
    )
    (net (code "17") (name "/NO6") (class "Default")
      (node (ref "P10") (pin "12") (pinfunction "12_12") (pintype "passive"))
      (node (ref "R32") (pin "1") (pinfunction "1_1") (pintype "passive"))
      (node (ref "U2") (pin "64") (pinfunction "PD3_64") (pintype "bidirectional"))
    )
    (net (code "18") (name "/OSC0") (class "Default")
      (node (ref "C18") (pin "2") (pinfunction "2_2") (pintype "passive"))
      (node (ref "U2") (pin "40") (pinfunction "OSC0_40") (pintype "input"))
      (node (ref "X1") (pin "1") (pintype "passive"))
    )
    (net (code "19") (name "/OSC1") (class "Default")
      (node (ref "C19") (pin "2") (pinfunction "2_2") (pintype "passive"))
      (node (ref "U2") (pin "41") (pinfunction "OSC1_41") (pintype "output"))
      (node (ref "X1") (pin "3") (pintype "passive"))
    )
    (net (code "20") (name "/PWM_A") (class "Default")
      (node (ref "P6") (pin "2") (pinfunction "PWM_2") (pintype "passive"))
      (node (ref "U2") (pin "23") (pinfunction "PA6_23") (pintype "bidirectional"))
    )
    (net (code "21") (name "/PWM_B") (class "Default")
      (node (ref "P7") (pin "2") (pinfunction "PWM_2") (pintype "passive"))
      (node (ref "U2") (pin "24") (pinfunction "PA7_24") (pintype "bidirectional"))
    )
    (net (code "22") (name "/PWM_C") (class "Default")
      (node (ref "P8") (pin "2") (pinfunction "PWM_2") (pintype "passive"))
      (node (ref "U2") (pin "28") (pinfunction "PF0_28") (pintype "bidirectional"))
    )
    (net (code "23") (name "/RESET") (class "Default")
      (node (ref "C27") (pin "2") (pinfunction "2_2") (pintype "passive"))
      (node (ref "R3") (pin "2") (pinfunction "2_2") (pintype "passive"))
      (node (ref "U2") (pin "38") (pinfunction "RESET_38") (pintype "input"))
    )
    (net (code "24") (name "/SHIELD") (class "Default")
      (node (ref "C2") (pin "2") (pinfunction "2_2") (pintype "passive"))
      (node (ref "R1") (pin "2") (pinfunction "2_2") (pintype "passive"))
      (node (ref "USB1") (pin "5") (pinfunction "SHIELD_5") (pintype "passive"))
      (node (ref "USB1") (pin "6") (pinfunction "SHIELD_6") (pintype "passive"))
    )
    (net (code "25") (name "/TCK") (class "Default")
      (node (ref "P1") (pin "2") (pinfunction "2_2") (pintype "passive"))
      (node (ref "R2") (pin "2") (pinfunction "2_2") (pintype "passive"))
      (node (ref "U2") (pin "52") (pinfunction "PC0/TCK/SWCLK_52") (pintype "bidirectional"))
    )
    (net (code "26") (name "/TDI") (class "Default")
      (node (ref "P1") (pin "4") (pinfunction "4_4") (pintype "passive"))
      (node (ref "U2") (pin "50") (pinfunction "PC2/TDI_50") (pintype "bidirectional"))
    )
    (net (code "27") (name "/TDO") (class "Default")
      (node (ref "P1") (pin "3") (pinfunction "3_3") (pintype "passive"))
      (node (ref "U2") (pin "49") (pinfunction "PC3/TDO/SWO_49") (pintype "bidirectional"))
    )
    (net (code "28") (name "/TMS") (class "Default")
      (node (ref "P1") (pin "5") (pinfunction "5_5") (pintype "passive"))
      (node (ref "U2") (pin "51") (pinfunction "PC1/TMS/SWDIO_51") (pintype "bidirectional"))
    )
    (net (code "29") (name "/USB RX LED") (class "Default")
      (node (ref "D2") (pin "2") (pinfunction "K_2") (pintype "passive"))
      (node (ref "U3") (pin "5") (pinfunction "CBUS2_5") (pintype "passive"))
    )
    (net (code "30") (name "/USB TX LED") (class "Default")
      (node (ref "D1") (pin "2") (pinfunction "K_2") (pintype "passive"))
      (node (ref "U3") (pin "11") (pinfunction "CBUS1_11") (pintype "passive"))
    )
    (net (code "31") (name "/USB_RX") (class "Default")
      (node (ref "R4") (pin "1") (pinfunction "1_1") (pintype "passive"))
      (node (ref "U2") (pin "17") (pinfunction "PA0/U0RX_17") (pintype "bidirectional"))
      (node (ref "U3") (pin "15") (pinfunction "TXD_15") (pintype "passive"))
    )
    (net (code "32") (name "/USB_TX") (class "Default")
      (node (ref "R5") (pin "1") (pinfunction "1_1") (pintype "passive"))
      (node (ref "U2") (pin "18") (pinfunction "PA1/U0TX_18") (pintype "bidirectional"))
      (node (ref "U3") (pin "2") (pinfunction "RXD_2") (pintype "passive"))
    )
    (net (code "33") (name "/VCORE") (class "Default")
      (node (ref "C24") (pin "2") (pinfunction "2_2") (pintype "passive"))
      (node (ref "C25") (pin "2") (pinfunction "2_2") (pintype "passive"))
      (node (ref "C26") (pin "2") (pinfunction "2_2") (pintype "passive"))
      (node (ref "U2") (pin "25") (pinfunction "VDDC_25") (pintype "power_in"))
      (node (ref "U2") (pin "56") (pinfunction "VDDC_56") (pintype "power_in"))
    )
    (net (code "34") (name "GND") (class "Default")
      (node (ref "C1") (pin "2") (pinfunction "2_2") (pintype "passive"))
      (node (ref "C10") (pin "2") (pinfunction "2_2") (pintype "passive"))
      (node (ref "C11") (pin "2") (pinfunction "2_2") (pintype "passive"))
      (node (ref "C12") (pin "2") (pinfunction "2_2") (pintype "passive"))
      (node (ref "C13") (pin "1") (pinfunction "1_1") (pintype "passive"))
      (node (ref "C14") (pin "1") (pinfunction "1_1") (pintype "passive"))
      (node (ref "C15") (pin "1") (pinfunction "1_1") (pintype "passive"))
      (node (ref "C16") (pin "1") (pinfunction "1_1") (pintype "passive"))
      (node (ref "C17") (pin "1") (pinfunction "1_1") (pintype "passive"))
      (node (ref "C18") (pin "1") (pinfunction "1_1") (pintype "passive"))
      (node (ref "C19") (pin "1") (pinfunction "1_1") (pintype "passive"))
      (node (ref "C2") (pin "1") (pinfunction "1_1") (pintype "passive"))
      (node (ref "C20") (pin "1") (pinfunction "1_1") (pintype "passive"))
      (node (ref "C21") (pin "1") (pinfunction "1_1") (pintype "passive"))
      (node (ref "C22") (pin "1") (pinfunction "1_1") (pintype "passive"))
      (node (ref "C23") (pin "1") (pinfunction "1_1") (pintype "passive"))
      (node (ref "C24") (pin "1") (pinfunction "1_1") (pintype "passive"))
      (node (ref "C25") (pin "1") (pinfunction "1_1") (pintype "passive"))
      (node (ref "C26") (pin "1") (pinfunction "1_1") (pintype "passive"))
      (node (ref "C27") (pin "1") (pinfunction "1_1") (pintype "passive"))
      (node (ref "C28") (pin "1") (pinfunction "1_1") (pintype "passive"))
      (node (ref "C29") (pin "1") (pinfunction "1_1") (pintype "passive"))
      (node (ref "C3") (pin "1") (pinfunction "1_1") (pintype "passive"))
      (node (ref "C4") (pin "1") (pinfunction "1_1") (pintype "passive"))
      (node (ref "C5") (pin "1") (pinfunction "1_1") (pintype "passive"))
      (node (ref "C6") (pin "1") (pinfunction "1_1") (pintype "passive"))
      (node (ref "C7") (pin "2") (pinfunction "2_2") (pintype "passive"))
      (node (ref "C8") (pin "2") (pinfunction "2_2") (pintype "passive"))
      (node (ref "C9") (pin "1") (pinfunction "1_1") (pintype "passive"))
      (node (ref "P1") (pin "1") (pinfunction "1_1") (pintype "passive"))
      (node (ref "P10") (pin "1") (pinfunction "1_1") (pintype "passive"))
      (node (ref "P10") (pin "2") (pinfunction "2_2") (pintype "passive"))
      (node (ref "P10") (pin "3") (pinfunction "3_3") (pintype "passive"))
      (node (ref "P10") (pin "4") (pinfunction "4_4") (pintype "passive"))
      (node (ref "P10") (pin "5") (pinfunction "5_5") (pintype "passive"))
      (node (ref "P10") (pin "6") (pinfunction "6_6") (pintype "passive"))
      (node (ref "P2") (pin "1") (pinfunction "GND_1") (pintype "passive"))
      (node (ref "P3") (pin "1") (pinfunction "GND_1") (pintype "passive"))
      (node (ref "P4") (pin "1") (pinfunction "GND_1") (pintype "passive"))
      (node (ref "P5") (pin "5") (pinfunction "GND_5") (pintype "passive"))
      (node (ref "P5") (pin "6") (pinfunction "GND_6") (pintype "passive"))
      (node (ref "P6") (pin "1") (pinfunction "GND_1") (pintype "passive"))
      (node (ref "P7") (pin "1") (pinfunction "GND_1") (pintype "passive"))
      (node (ref "P8") (pin "1") (pinfunction "GND_1") (pintype "passive"))
      (node (ref "P9") (pin "1") (pinfunction "1_1") (pintype "passive"))
      (node (ref "P9") (pin "2") (pinfunction "2_2") (pintype "passive"))
      (node (ref "P9") (pin "3") (pinfunction "3_3") (pintype "passive"))
      (node (ref "R1") (pin "1") (pinfunction "1_1") (pintype "passive"))
      (node (ref "U1") (pin "2") (pinfunction "GND_2") (pintype "power_in"))
      (node (ref "U1") (pin "4") (pinfunction "GND_4") (pintype "power_in"))
      (node (ref "U2") (pin "12") (pinfunction "GND_12") (pintype "power_in"))
      (node (ref "U2") (pin "27") (pinfunction "GND_27") (pintype "power_in"))
      (node (ref "U2") (pin "3") (pinfunction "GNDA_3") (pintype "power_in"))
      (node (ref "U2") (pin "32") (pinfunction "WAKE_32") (pintype "input"))
      (node (ref "U2") (pin "34") (pinfunction "XOSC0_34") (pintype "input"))
      (node (ref "U2") (pin "35") (pinfunction "GNDX_35") (pintype "power_in"))
      (node (ref "U2") (pin "39") (pinfunction "GND_39") (pintype "power_in"))
      (node (ref "U2") (pin "55") (pinfunction "GND_55") (pintype "power_in"))
      (node (ref "U3") (pin "13") (pinfunction "GND_13") (pintype "passive"))
      (node (ref "U3") (pin "17") (pinfunction "GND_17") (pintype "passive"))
      (node (ref "U3") (pin "3") (pinfunction "GND_3") (pintype "passive"))
      (node (ref "USB1") (pin "4") (pinfunction "GND_4") (pintype "power_in"))
      (node (ref "X1") (pin "2") (pinfunction "CASE_2") (pintype "passive"))
      (node (ref "X1") (pin "4") (pinfunction "CASE_4") (pintype "passive"))
    )
    (net (code "35") (name "Net-(D1-A)") (class "Default")
      (node (ref "D1") (pin "1") (pinfunction "A_1") (pintype "passive"))
      (node (ref "R13") (pin "1") (pinfunction "1_1") (pintype "passive"))
    )
    (net (code "36") (name "Net-(D2-A)") (class "Default")
      (node (ref "D2") (pin "1") (pinfunction "A_1") (pintype "passive"))
      (node (ref "R14") (pin "1") (pinfunction "1_1") (pintype "passive"))
    )
    (net (code "37") (name "Net-(U3-CTS#)") (class "Default")
      (node (ref "R7") (pin "1") (pinfunction "1_1") (pintype "passive"))
      (node (ref "U3") (pin "4") (pinfunction "CTS#_4") (pintype "passive"))
    )
    (net (code "38") (name "Net-(U3-RTS#)") (class "Default")
      (node (ref "R6") (pin "1") (pinfunction "1_1") (pintype "passive"))
      (node (ref "U3") (pin "16") (pinfunction "RTS#_16") (pintype "passive"))
    )
    (net (code "39") (name "Net-(U3-USBDM)") (class "Default")
      (node (ref "R8") (pin "2") (pinfunction "2_2") (pintype "passive"))
      (node (ref "U3") (pin "7") (pinfunction "USBDM_7") (pintype "passive"))
    )
    (net (code "40") (name "Net-(U3-USBDP)") (class "Default")
      (node (ref "R9") (pin "2") (pinfunction "2_2") (pintype "passive"))
      (node (ref "U3") (pin "6") (pinfunction "USBDP_6") (pintype "passive"))
    )
    (net (code "41") (name "VBUS") (class "Default")
      (node (ref "C1") (pin "1") (pinfunction "1_1") (pintype "passive"))
      (node (ref "C3") (pin "2") (pinfunction "2_2") (pintype "passive"))
      (node (ref "L1") (pin "1") (pinfunction "1_1") (pintype "passive"))
      (node (ref "USB1") (pin "1") (pinfunction "VDD_1") (pintype "power_in"))
    )
    (net (code "42") (name "unconnected-(U2-HIB-Pad33)") (class "Default")
      (node (ref "U2") (pin "33") (pinfunction "HIB_33") (pintype "output+no_connect"))
    )
    (net (code "43") (name "unconnected-(U2-PA2{slash}SSI0CLK-Pad19)") (class "Default")
      (node (ref "U2") (pin "19") (pinfunction "PA2/SSI0CLK_19") (pintype "bidirectional"))
    )
    (net (code "44") (name "unconnected-(U2-PA3{slash}SSI0FSS-Pad20)") (class "Default")
      (node (ref "U2") (pin "20") (pinfunction "PA3/SSI0FSS_20") (pintype "bidirectional"))
    )
    (net (code "45") (name "unconnected-(U2-PA4{slash}SSI0RX-Pad21)") (class "Default")
      (node (ref "U2") (pin "21") (pinfunction "PA4/SSI0RX_21") (pintype "bidirectional"))
    )
    (net (code "46") (name "unconnected-(U2-PA5{slash}SSI0TX-Pad22)") (class "Default")
      (node (ref "U2") (pin "22") (pinfunction "PA5/SSI0TX_22") (pintype "bidirectional"))
    )
    (net (code "47") (name "unconnected-(U2-PB0{slash}USB0ID-Pad45)") (class "Default")
      (node (ref "U2") (pin "45") (pinfunction "PB0/USB0ID_45") (pintype "bidirectional"))
    )
    (net (code "48") (name "unconnected-(U2-PB1{slash}USB0VBUS-Pad46)") (class "Default")
      (node (ref "U2") (pin "46") (pinfunction "PB1/USB0VBUS_46") (pintype "bidirectional"))
    )
    (net (code "49") (name "unconnected-(U2-PB2{slash}I2COSCL-Pad47)") (class "Default")
      (node (ref "U2") (pin "47") (pinfunction "PB2/I2COSCL_47") (pintype "bidirectional"))
    )
    (net (code "50") (name "unconnected-(U2-PB3{slash}I2COSDA-Pad48)") (class "Default")
      (node (ref "U2") (pin "48") (pinfunction "PB3/I2COSDA_48") (pintype "bidirectional"))
    )
    (net (code "51") (name "unconnected-(U2-PB6-Pad1)") (class "Default")
      (node (ref "U2") (pin "1") (pinfunction "PB6_1") (pintype "bidirectional"))
    )
    (net (code "52") (name "unconnected-(U2-PB7-Pad4)") (class "Default")
      (node (ref "U2") (pin "4") (pinfunction "PB7_4") (pintype "bidirectional"))
    )
    (net (code "53") (name "unconnected-(U2-PC4-Pad16)") (class "Default")
      (node (ref "U2") (pin "16") (pinfunction "PC4_16") (pintype "bidirectional"))
    )
    (net (code "54") (name "unconnected-(U2-PC5-Pad15)") (class "Default")
      (node (ref "U2") (pin "15") (pinfunction "PC5_15") (pintype "bidirectional"))
    )
    (net (code "55") (name "unconnected-(U2-PC6-Pad14)") (class "Default")
      (node (ref "U2") (pin "14") (pinfunction "PC6_14") (pintype "bidirectional"))
    )
    (net (code "56") (name "unconnected-(U2-PC7-Pad13)") (class "Default")
      (node (ref "U2") (pin "13") (pinfunction "PC7_13") (pintype "bidirectional"))
    )
    (net (code "57") (name "unconnected-(U2-PD4-Pad43)") (class "Default")
      (node (ref "U2") (pin "43") (pinfunction "PD4_43") (pintype "bidirectional"))
    )
    (net (code "58") (name "unconnected-(U2-PD5-Pad44)") (class "Default")
      (node (ref "U2") (pin "44") (pinfunction "PD5_44") (pintype "bidirectional"))
    )
    (net (code "59") (name "unconnected-(U2-PD6-Pad53)") (class "Default")
      (node (ref "U2") (pin "53") (pinfunction "PD6_53") (pintype "bidirectional"))
    )
    (net (code "60") (name "unconnected-(U2-PD7-Pad10)") (class "Default")
      (node (ref "U2") (pin "10") (pinfunction "PD7_10") (pintype "bidirectional"))
    )
    (net (code "61") (name "unconnected-(U2-PE0-Pad9)") (class "Default")
      (node (ref "U2") (pin "9") (pinfunction "PE0_9") (pintype "bidirectional"))
    )
    (net (code "62") (name "unconnected-(U2-PE1-Pad8)") (class "Default")
      (node (ref "U2") (pin "8") (pinfunction "PE1_8") (pintype "bidirectional"))
    )
    (net (code "63") (name "unconnected-(U2-PE2-Pad7)") (class "Default")
      (node (ref "U2") (pin "7") (pinfunction "PE2_7") (pintype "bidirectional"))
    )
    (net (code "64") (name "unconnected-(U2-PE3-Pad6)") (class "Default")
      (node (ref "U2") (pin "6") (pinfunction "PE3_6") (pintype "bidirectional"))
    )
    (net (code "65") (name "unconnected-(U2-PF4-Pad5)") (class "Default")
      (node (ref "U2") (pin "5") (pinfunction "PF4_5") (pintype "bidirectional"))
    )
    (net (code "66") (name "unconnected-(U2-XOSC1-Pad36)") (class "Default")
      (node (ref "U2") (pin "36") (pinfunction "XOSC1_36") (pintype "output+no_connect"))
    )
    (net (code "67") (name "unconnected-(U3-CBUS0-Pad12)") (class "Default")
      (node (ref "U3") (pin "12") (pinfunction "CBUS0_12") (pintype "passive+no_connect"))
    )
    (net (code "68") (name "unconnected-(U3-CBUS3-Pad14)") (class "Default")
      (node (ref "U3") (pin "14") (pinfunction "CBUS3_14") (pintype "passive+no_connect"))
    )
  )
)
